# BOOSTXL-K350QVG-S1.net
KiCad netlist of a schematic drawn in Altium Designer
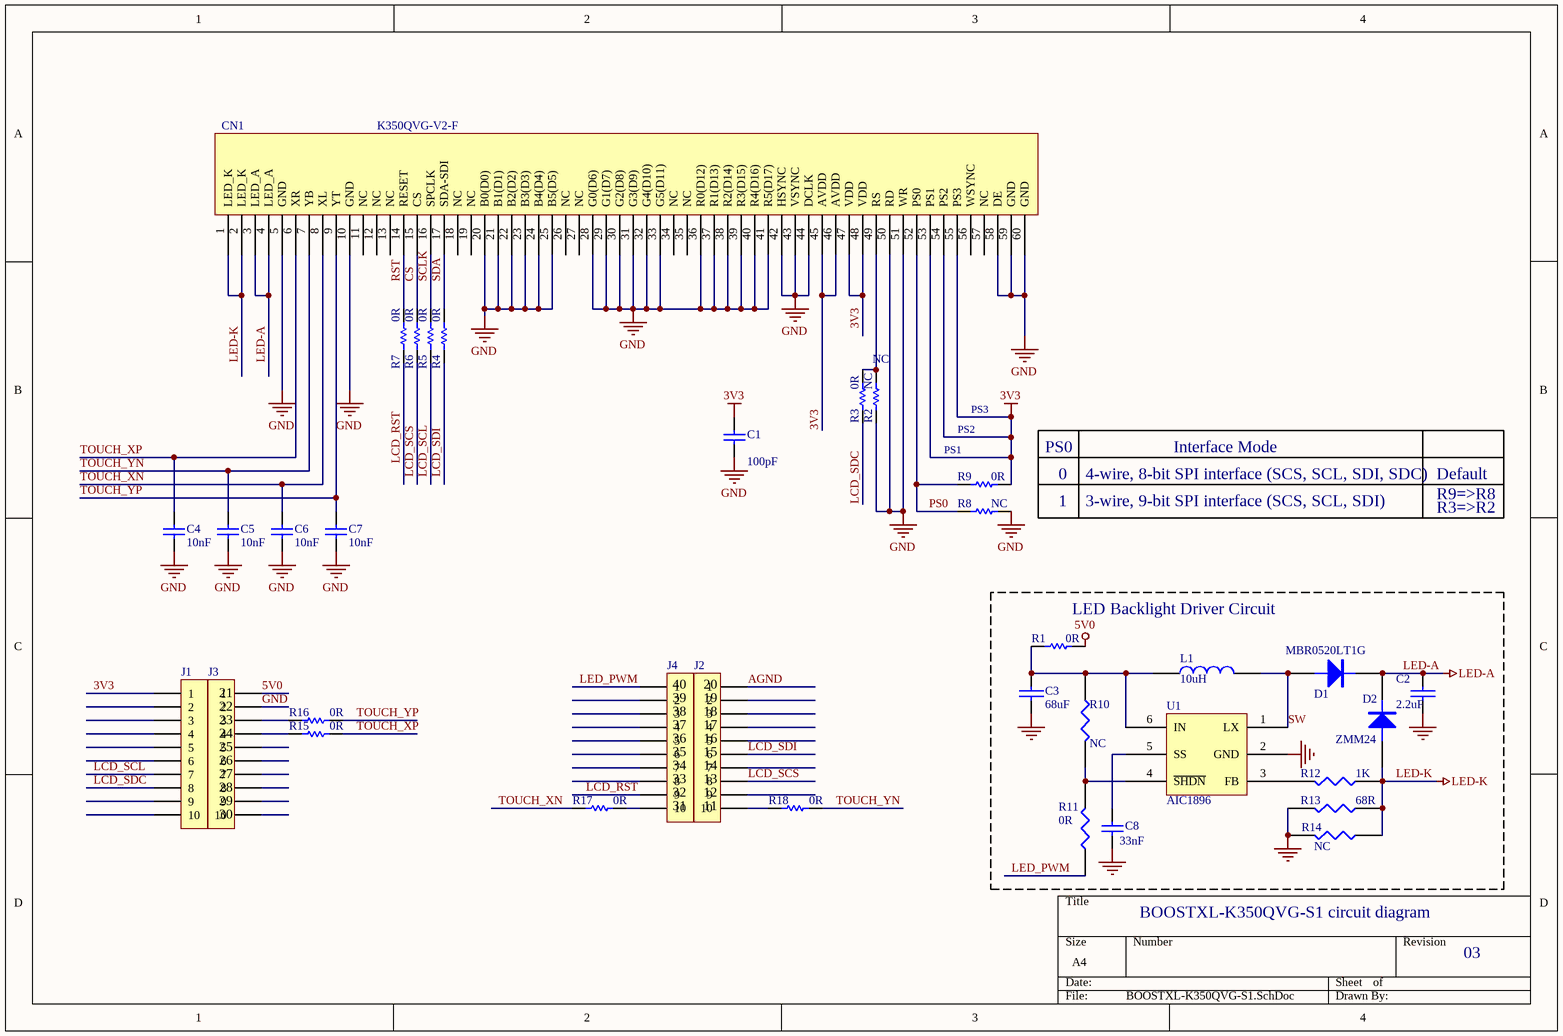
[diagram p0: BOOSTXL-K350QVG-S1.SchDoc]

(export (version "E")
  (design (tool "Eeschema 10.0.6"))
  (components
    (comp (ref "C1")
      (value "100pF")
      (footprint "1608[0603]")
      (description "Capacitor (Semiconductor SIM Model)")
      (fields (field (name "Comment") "0.1uF") (field (name "PUBLISHER") "Altium Limited"))
      (libsource (lib "Miscellaneous Devices") (part "Cap Semi"))
    )
    (comp (ref "C2")
      (value "2.2uF")
      (footprint "3225[1210]")
      (description "Capacitor")
      (libsource (lib "*") (part "CAP"))
    )
    (comp (ref "C3")
      (value "68uF")
      (footprint "TAN-C")
      (description "Capacitor")
      (libsource (lib "*") (part "CAP"))
    )
    (comp (ref "C4")
      (value "10nF")
      (footprint "1608[0603]")
      (description "Capacitor (Semiconductor SIM Model)")
      (fields (field (name "PUBLISHER") "Altium Limited"))
      (libsource (lib "Miscellaneous Devices") (part "Cap Semi"))
    )
    (comp (ref "C5")
      (value "10nF")
      (footprint "1608[0603]")
      (description "Capacitor (Semiconductor SIM Model)")
      (fields (field (name "PUBLISHER") "Altium Limited"))
      (libsource (lib "Miscellaneous Devices") (part "Cap Semi"))
    )
    (comp (ref "C6")
      (value "10nF")
      (footprint "1608[0603]")
      (description "Capacitor (Semiconductor SIM Model)")
      (fields (field (name "PUBLISHER") "Altium Limited"))
      (libsource (lib "Miscellaneous Devices") (part "Cap Semi"))
    )
    (comp (ref "C7")
      (value "10nF")
      (footprint "1608[0603]")
      (description "Capacitor (Semiconductor SIM Model)")
      (fields (field (name "PUBLISHER") "Altium Limited"))
      (libsource (lib "Miscellaneous Devices") (part "Cap Semi"))
    )
    (comp (ref "C8")
      (value "33nF")
      (footprint "1608[0603]")
      (description "Capacitor (Semiconductor SIM Model)")
      (fields (field (name "PUBLISHER") "Altium Limited"))
      (libsource (lib "Miscellaneous Devices") (part "Cap Semi"))
    )
    (comp (ref "CN1")
      (value "K350QVG-V2-F")
      (footprint "CON-K350-60")
      (libsource (lib "KEDlib") (part "K350QVG"))
    )
    (comp (ref "D1")
      (value "MBR0520LT1G")
      (footprint "DIODE")
      (description "Diode")
      (libsource (lib "*") (part "DIODE"))
    )
    (comp (ref "D2")
      (value "ZMM24")
      (footprint "DIODE")
      (description "Diode")
      (libsource (lib "*") (part "DIODE"))
    )
    (comp (ref "J1")
      (value "Socket 10")
      (footprint "HDR1X10")
      (description "Header, 10-Pin")
      (fields (field (name "PUBLISHER") "Altium Limited"))
      (libsource (lib "EB-StellarisLaunchPad-LCD") (part "Header 10"))
    )
    (comp (ref "J2")
      (value "Socket 10")
      (footprint "HDR1X10")
      (description "Header, 10-Pin")
      (fields (field (name "PUBLISHER") "Altium Limited"))
      (libsource (lib "") (part "Header 10_1"))
    )
    (comp (ref "J3")
      (value "Socket 10")
      (footprint "HDR1X10")
      (description "Header, 10-Pin")
      (fields (field (name "PUBLISHER") "Altium Limited"))
      (libsource (lib "") (part "Header 10_1"))
    )
    (comp (ref "J4")
      (value "Socket 10")
      (footprint "HDR1X10")
      (description "Header, 10-Pin")
      (fields (field (name "PUBLISHER") "Altium Limited"))
      (libsource (lib "EB-StellarisLaunchPad-LCD") (part "Header 10"))
    )
    (comp (ref "L1") (value "10uH") (footprint "IND") (libsource (lib "*") (part "INDUCTOR")))
    (comp (ref "R1")
      (value "0R")
      (footprint "1608[0603]")
      (description "Semiconductor Resistor")
      (fields (field (name "PUBLISHER") "Altium Limited"))
      (libsource (lib "Miscellaneous Devices") (part "Res Semi"))
    )
    (comp (ref "R2")
      (value "NC")
      (footprint "1608[0603]")
      (description "Semiconductor Resistor")
      (fields (field (name "ALTIUM_VALUE") "NC") (field (name "PUBLISHER") "Altium Limited"))
      (libsource (lib "Miscellaneous Devices") (part "Res Semi"))
    )
    (comp (ref "R3")
      (value "0R")
      (footprint "1608[0603]")
      (description "Semiconductor Resistor")
      (fields (field (name "PUBLISHER") "Altium Limited"))
      (libsource (lib "Miscellaneous Devices") (part "Res Semi"))
    )
    (comp (ref "R4")
      (value "0R")
      (footprint "1608[0603]")
      (description "Semiconductor Resistor")
      (fields (field (name "PUBLISHER") "Altium Limited"))
      (libsource (lib "Miscellaneous Devices") (part "Res Semi"))
    )
    (comp (ref "R5")
      (value "0R")
      (footprint "1608[0603]")
      (description "Semiconductor Resistor")
      (fields (field (name "PUBLISHER") "Altium Limited"))
      (libsource (lib "Miscellaneous Devices") (part "Res Semi"))
    )
    (comp (ref "R6")
      (value "0R")
      (footprint "1608[0603]")
      (description "Semiconductor Resistor")
      (fields (field (name "PUBLISHER") "Altium Limited"))
      (libsource (lib "Miscellaneous Devices") (part "Res Semi"))
    )
    (comp (ref "R7")
      (value "0R")
      (footprint "1608[0603]")
      (description "Semiconductor Resistor")
      (fields (field (name "PUBLISHER") "Altium Limited"))
      (libsource (lib "Miscellaneous Devices") (part "Res Semi"))
    )
    (comp (ref "R8")
      (value "NC")
      (footprint "1608[0603]")
      (description "Semiconductor Resistor")
      (fields (field (name "PUBLISHER") "Altium Limited"))
      (libsource (lib "Miscellaneous Devices") (part "Res Semi"))
    )
    (comp (ref "R9")
      (value "0R")
      (footprint "1608[0603]")
      (description "Semiconductor Resistor")
      (fields (field (name "PUBLISHER") "Altium Limited"))
      (libsource (lib "Miscellaneous Devices") (part "Res Semi"))
    )
    (comp (ref "R10") (value "NC") (footprint "1608[0603]") (libsource (lib "*") (part "RES1")))
    (comp (ref "R11") (value "0R") (footprint "1608[0603]") (libsource (lib "*") (part "RES1")))
    (comp (ref "R12") (value "1K") (footprint "1608[0603]") (libsource (lib "*") (part "RES1")))
    (comp (ref "R13") (value "68R") (footprint "1608[0603]") (libsource (lib "*") (part "RES1")))
    (comp (ref "R14") (value "NC") (footprint "1608[0603]") (libsource (lib "*") (part "RES1")))
    (comp (ref "R15")
      (value "0R")
      (footprint "1608[0603]")
      (description "Semiconductor Resistor")
      (fields (field (name "PUBLISHER") "Altium Limited"))
      (libsource (lib "Miscellaneous Devices") (part "Res Semi"))
    )
    (comp (ref "R16")
      (value "0R")
      (footprint "1608[0603]")
      (description "Semiconductor Resistor")
      (fields (field (name "PUBLISHER") "Altium Limited"))
      (libsource (lib "Miscellaneous Devices") (part "Res Semi"))
    )
    (comp (ref "R17")
      (value "0R")
      (footprint "1608[0603]")
      (description "Semiconductor Resistor")
      (fields (field (name "PUBLISHER") "Altium Limited"))
      (libsource (lib "Miscellaneous Devices") (part "Res Semi"))
    )
    (comp (ref "R18")
      (value "0R")
      (footprint "1608[0603]")
      (description "Semiconductor Resistor")
      (fields (field (name "PUBLISHER") "Altium Limited"))
      (libsource (lib "Miscellaneous Devices") (part "Res Semi"))
    )
    (comp (ref "U1")
      (value "AIC1896")
      (footprint "SOT-23-6")
      (libsource (lib "EB-StellarisLaunchPad-LCD") (part "AIC1896"))
    )
  )
  (nets
    (net (code "1") (name "/CS") (class "Default")
      (node (ref "CN1") (pin "15") (pinfunction "CS_15") (pintype "passive"))
      (node (ref "R6") (pin "2") (pinfunction "2_2") (pintype "passive"))
    )
    (net (code "2") (name "/LCD_RST") (class "Default")
      (node (ref "J4") (pin "9") (pinfunction "9_9") (pintype "passive"))
      (node (ref "R7") (pin "1") (pinfunction "1_1") (pintype "passive"))
    )
    (net (code "3") (name "/LCD_SCL") (class "Default")
      (node (ref "J1") (pin "7") (pinfunction "7_7") (pintype "passive"))
      (node (ref "R5") (pin "1") (pinfunction "1_1") (pintype "passive"))
    )
    (net (code "4") (name "/LCD_SCS") (class "Default")
      (node (ref "J2") (pin "8") (pinfunction "8_8") (pintype "passive"))
      (node (ref "R6") (pin "1") (pinfunction "1_1") (pintype "passive"))
    )
    (net (code "5") (name "/LCD_SDC") (class "Default")
      (node (ref "J1") (pin "8") (pinfunction "8_8") (pintype "passive"))
      (node (ref "R3") (pin "1") (pinfunction "1_1") (pintype "passive"))
    )
    (net (code "6") (name "/LCD_SDI") (class "Default")
      (node (ref "J2") (pin "6") (pinfunction "6_6") (pintype "passive"))
      (node (ref "R4") (pin "1") (pinfunction "1_1") (pintype "passive"))
    )
    (net (code "7") (name "/LED_PWM") (class "Default")
      (node (ref "J4") (pin "1") (pinfunction "1_1") (pintype "passive"))
      (node (ref "R11") (pin "1") (pinfunction "1_1") (pintype "passive"))
    )
    (net (code "8") (name "/PS0") (class "Default")
      (node (ref "CN1") (pin "52") (pinfunction "PS0_52") (pintype "passive"))
      (node (ref "R8") (pin "1") (pinfunction "1_1") (pintype "passive"))
      (node (ref "R9") (pin "1") (pinfunction "1_1") (pintype "passive"))
    )
    (net (code "9") (name "/RST") (class "Default")
      (node (ref "CN1") (pin "14") (pinfunction "RESET_14") (pintype "passive"))
      (node (ref "R7") (pin "2") (pinfunction "2_2") (pintype "passive"))
    )
    (net (code "10") (name "/SCLK") (class "Default")
      (node (ref "CN1") (pin "16") (pinfunction "SPCLK_16") (pintype "passive"))
      (node (ref "R5") (pin "2") (pinfunction "2_2") (pintype "passive"))
    )
    (net (code "11") (name "/SDA") (class "Default")
      (node (ref "CN1") (pin "17") (pinfunction "SDA-SDI_17") (pintype "passive"))
      (node (ref "R4") (pin "2") (pinfunction "2_2") (pintype "passive"))
    )
    (net (code "12") (name "/SW") (class "Default")
      (node (ref "D1") (pin "A") (pinfunction "A_A") (pintype "passive"))
      (node (ref "L1") (pin "2") (pinfunction "2_2") (pintype "passive"))
      (node (ref "U1") (pin "1") (pinfunction "LX_1") (pintype "passive"))
    )
    (net (code "13") (name "/TOUCH_XN") (class "Default")
      (node (ref "C6") (pin "2") (pinfunction "2_2") (pintype "passive"))
      (node (ref "CN1") (pin "8") (pinfunction "XL_8") (pintype "passive"))
      (node (ref "R17") (pin "1") (pinfunction "1_1") (pintype "passive"))
    )
    (net (code "14") (name "/TOUCH_XP") (class "Default")
      (node (ref "C4") (pin "2") (pinfunction "2_2") (pintype "passive"))
      (node (ref "CN1") (pin "6") (pinfunction "XR_6") (pintype "passive"))
      (node (ref "R15") (pin "2") (pinfunction "2_2") (pintype "passive"))
    )
    (net (code "15") (name "/TOUCH_YN") (class "Default")
      (node (ref "C5") (pin "2") (pinfunction "2_2") (pintype "passive"))
      (node (ref "CN1") (pin "7") (pinfunction "YB_7") (pintype "passive"))
      (node (ref "R18") (pin "2") (pinfunction "2_2") (pintype "passive"))
    )
    (net (code "16") (name "/TOUCH_YP") (class "Default")
      (node (ref "C7") (pin "2") (pinfunction "2_2") (pintype "passive"))
      (node (ref "CN1") (pin "9") (pinfunction "YT_9") (pintype "passive"))
      (node (ref "R16") (pin "2") (pinfunction "2_2") (pintype "passive"))
    )
    (net (code "17") (name "3V3") (class "Default")
      (node (ref "C1") (pin "2") (pinfunction "2_2") (pintype "passive"))
      (node (ref "CN1") (pin "45") (pinfunction "AVDD_45") (pintype "passive"))
      (node (ref "CN1") (pin "46") (pinfunction "AVDD_46") (pintype "passive"))
      (node (ref "CN1") (pin "47") (pinfunction "VDD_47") (pintype "passive"))
      (node (ref "CN1") (pin "48") (pinfunction "VDD_48") (pintype "passive"))
      (node (ref "CN1") (pin "53") (pinfunction "PS1_53") (pintype "passive"))
      (node (ref "CN1") (pin "54") (pinfunction "PS2_54") (pintype "passive"))
      (node (ref "CN1") (pin "55") (pinfunction "PS3_55") (pintype "passive"))
      (node (ref "J1") (pin "1") (pinfunction "1_1") (pintype "passive"))
      (node (ref "R9") (pin "2") (pinfunction "2_2") (pintype "passive"))
    )
    (net (code "18") (name "5V0") (class "Default")
      (node (ref "J3") (pin "1") (pinfunction "1_1") (pintype "passive"))
      (node (ref "R1") (pin "2") (pinfunction "2_2") (pintype "passive"))
    )
    (net (code "19") (name "AGND") (class "Default")
      (node (ref "C2") (pin "1") (pinfunction "1_1") (pintype "passive"))
      (node (ref "C3") (pin "2") (pinfunction "2_2") (pintype "passive"))
      (node (ref "C8") (pin "1") (pinfunction "1_1") (pintype "passive"))
      (node (ref "J2") (pin "1") (pinfunction "1_1") (pintype "passive"))
      (node (ref "R13") (pin "2") (pinfunction "2_2") (pintype "passive"))
      (node (ref "R14") (pin "2") (pinfunction "2_2") (pintype "passive"))
    )
    (net (code "20") (name "GND") (class "Default")
      (node (ref "C1") (pin "1") (pinfunction "1_1") (pintype "passive"))
      (node (ref "C4") (pin "1") (pinfunction "1_1") (pintype "passive"))
      (node (ref "C5") (pin "1") (pinfunction "1_1") (pintype "passive"))
      (node (ref "C6") (pin "1") (pinfunction "1_1") (pintype "passive"))
      (node (ref "C7") (pin "1") (pinfunction "1_1") (pintype "passive"))
      (node (ref "CN1") (pin "10") (pinfunction "GND_10") (pintype "passive"))
      (node (ref "CN1") (pin "20") (pinfunction "B0(D0)_20") (pintype "passive"))
      (node (ref "CN1") (pin "21") (pinfunction "B1(D1)_21") (pintype "passive"))
      (node (ref "CN1") (pin "22") (pinfunction "B2(D2)_22") (pintype "passive"))
      (node (ref "CN1") (pin "23") (pinfunction "B3(D3)_23") (pintype "passive"))
      (node (ref "CN1") (pin "24") (pinfunction "B4(D4)_24") (pintype "passive"))
      (node (ref "CN1") (pin "25") (pinfunction "B5(D5)_25") (pintype "passive"))
      (node (ref "CN1") (pin "28") (pinfunction "G0(D6)_28") (pintype "passive"))
      (node (ref "CN1") (pin "29") (pinfunction "G1(D7)_29") (pintype "passive"))
      (node (ref "CN1") (pin "30") (pinfunction "G2(D8)_30") (pintype "passive"))
      (node (ref "CN1") (pin "31") (pinfunction "G3(D9)_31") (pintype "passive"))
      (node (ref "CN1") (pin "32") (pinfunction "G4(D10)_32") (pintype "passive"))
      (node (ref "CN1") (pin "33") (pinfunction "G5(D11)_33") (pintype "passive"))
      (node (ref "CN1") (pin "36") (pinfunction "R0(D12)_36") (pintype "passive"))
      (node (ref "CN1") (pin "37") (pinfunction "R1(D13)_37") (pintype "passive"))
      (node (ref "CN1") (pin "38") (pinfunction "R2(D14)_38") (pintype "passive"))
      (node (ref "CN1") (pin "39") (pinfunction "R3(D15)_39") (pintype "passive"))
      (node (ref "CN1") (pin "40") (pinfunction "R4(D16)_40") (pintype "passive"))
      (node (ref "CN1") (pin "41") (pinfunction "R5(D17)_41") (pintype "passive"))
      (node (ref "CN1") (pin "42") (pinfunction "HSYNC_42") (pintype "passive"))
      (node (ref "CN1") (pin "43") (pinfunction "VSYNC_43") (pintype "passive"))
      (node (ref "CN1") (pin "44") (pinfunction "DCLK_44") (pintype "passive"))
      (node (ref "CN1") (pin "5") (pinfunction "GND_5") (pintype "passive"))
      (node (ref "CN1") (pin "50") (pinfunction "RD_50") (pintype "passive"))
      (node (ref "CN1") (pin "51") (pinfunction "WR_51") (pintype "passive"))
      (node (ref "CN1") (pin "58") (pinfunction "DE_58") (pintype "passive"))
      (node (ref "CN1") (pin "59") (pinfunction "GND_59") (pintype "passive"))
      (node (ref "CN1") (pin "60") (pinfunction "GND_60") (pintype "passive"))
      (node (ref "J3") (pin "2") (pinfunction "2_2") (pintype "passive"))
      (node (ref "R2") (pin "1") (pinfunction "1_1") (pintype "passive"))
      (node (ref "R8") (pin "2") (pinfunction "2_2") (pintype "passive"))
      (node (ref "U1") (pin "2") (pinfunction "GND_2") (pintype "passive"))
    )
    (net (code "21") (name "LED-A") (class "Default")
      (node (ref "C2") (pin "2") (pinfunction "2_2") (pintype "passive"))
      (node (ref "CN1") (pin "3") (pinfunction "LED_A_3") (pintype "passive"))
      (node (ref "CN1") (pin "4") (pinfunction "LED_A_4") (pintype "passive"))
      (node (ref "D1") (pin "K") (pinfunction "K_K") (pintype "passive"))
      (node (ref "D2") (pin "K") (pinfunction "K_K") (pintype "passive"))
    )
    (net (code "22") (name "LED-K") (class "Default")
      (node (ref "CN1") (pin "1") (pinfunction "LED_K_1") (pintype "passive"))
      (node (ref "CN1") (pin "2") (pinfunction "LED_K_2") (pintype "passive"))
      (node (ref "D2") (pin "A") (pinfunction "A_A") (pintype "passive"))
      (node (ref "R12") (pin "1") (pinfunction "1_1") (pintype "passive"))
      (node (ref "R13") (pin "1") (pinfunction "1_1") (pintype "passive"))
      (node (ref "R14") (pin "1") (pinfunction "1_1") (pintype "passive"))
    )
    (net (code "23") (name "Net-(CN1-RS)") (class "Default")
      (node (ref "CN1") (pin "49") (pinfunction "RS_49") (pintype "passive"))
      (node (ref "R2") (pin "2") (pinfunction "2_2") (pintype "passive"))
      (node (ref "R3") (pin "2") (pinfunction "2_2") (pintype "passive"))
    )
    (net (code "24") (name "Net-(J2-Pad10)") (class "Default")
      (node (ref "J2") (pin "10") (pinfunction "10_10") (pintype "passive"))
      (node (ref "R18") (pin "1") (pinfunction "1_1") (pintype "passive"))
    )
    (net (code "25") (name "Net-(J3-Pad3)") (class "Default")
      (node (ref "J3") (pin "3") (pinfunction "3_3") (pintype "passive"))
      (node (ref "R16") (pin "1") (pinfunction "1_1") (pintype "passive"))
    )
    (net (code "26") (name "Net-(J3-Pad4)") (class "Default")
      (node (ref "J3") (pin "4") (pinfunction "4_4") (pintype "passive"))
      (node (ref "R15") (pin "1") (pinfunction "1_1") (pintype "passive"))
    )
    (net (code "27") (name "Net-(J4-Pad10)") (class "Default")
      (node (ref "J4") (pin "10") (pinfunction "10_10") (pintype "passive"))
      (node (ref "R17") (pin "2") (pinfunction "2_2") (pintype "passive"))
    )
    (net (code "28") (name "Net-(U1-FB)") (class "Default")
      (node (ref "R12") (pin "2") (pinfunction "2_2") (pintype "passive"))
      (node (ref "U1") (pin "3") (pinfunction "FB_3") (pintype "passive"))
    )
    (net (code "29") (name "Net-(U1-IN)") (class "Default")
      (node (ref "C3") (pin "1") (pinfunction "1_1") (pintype "passive"))
      (node (ref "L1") (pin "1") (pinfunction "1_1") (pintype "passive"))
      (node (ref "R1") (pin "1") (pinfunction "1_1") (pintype "passive"))
      (node (ref "R10") (pin "1") (pinfunction "1_1") (pintype "passive"))
      (node (ref "U1") (pin "6") (pinfunction "IN_6") (pintype "passive"))
    )
    (net (code "30") (name "Net-(U1-SS)") (class "Default")
      (node (ref "C8") (pin "2") (pinfunction "2_2") (pintype "passive"))
      (node (ref "U1") (pin "5") (pinfunction "SS_5") (pintype "passive"))
    )
    (net (code "31") (name "Net-(U1-~{SHDN})") (class "Default")
      (node (ref "R10") (pin "2") (pinfunction "2_2") (pintype "passive"))
      (node (ref "R11") (pin "2") (pinfunction "2_2") (pintype "passive"))
      (node (ref "U1") (pin "4") (pinfunction "~{SHDN}_4") (pintype "passive"))
    )
    (net (code "32") (name "unconnected-(CN1-NC-Pad11)") (class "Default")
      (node (ref "CN1") (pin "11") (pinfunction "NC_11") (pintype "passive"))
    )
    (net (code "33") (name "unconnected-(CN1-NC-Pad12)") (class "Default")
      (node (ref "CN1") (pin "12") (pinfunction "NC_12") (pintype "passive"))
    )
    (net (code "34") (name "unconnected-(CN1-NC-Pad13)") (class "Default")
      (node (ref "CN1") (pin "13") (pinfunction "NC_13") (pintype "passive"))
    )
    (net (code "35") (name "unconnected-(CN1-NC-Pad18)") (class "Default")
      (node (ref "CN1") (pin "18") (pinfunction "NC_18") (pintype "passive"))
    )
    (net (code "36") (name "unconnected-(CN1-NC-Pad19)") (class "Default")
      (node (ref "CN1") (pin "19") (pinfunction "NC_19") (pintype "passive"))
    )
    (net (code "37") (name "unconnected-(CN1-NC-Pad26)") (class "Default")
      (node (ref "CN1") (pin "26") (pinfunction "NC_26") (pintype "passive"))
    )
    (net (code "38") (name "unconnected-(CN1-NC-Pad27)") (class "Default")
      (node (ref "CN1") (pin "27") (pinfunction "NC_27") (pintype "passive"))
    )
    (net (code "39") (name "unconnected-(CN1-NC-Pad34)") (class "Default")
      (node (ref "CN1") (pin "34") (pinfunction "NC_34") (pintype "passive"))
    )
    (net (code "40") (name "unconnected-(CN1-NC-Pad35)") (class "Default")
      (node (ref "CN1") (pin "35") (pinfunction "NC_35") (pintype "passive"))
    )
    (net (code "41") (name "unconnected-(CN1-NC-Pad57)") (class "Default")
      (node (ref "CN1") (pin "57") (pinfunction "NC_57") (pintype "passive"))
    )
    (net (code "42") (name "unconnected-(CN1-WSYNC-Pad56)") (class "Default")
      (node (ref "CN1") (pin "56") (pinfunction "WSYNC_56") (pintype "passive"))
    )
    (net (code "43") (name "unconnected-(J1-Pad2)") (class "Default")
      (node (ref "J1") (pin "2") (pinfunction "2_2") (pintype "passive"))
    )
    (net (code "44") (name "unconnected-(J1-Pad3)") (class "Default")
      (node (ref "J1") (pin "3") (pinfunction "3_3") (pintype "passive"))
    )
    (net (code "45") (name "unconnected-(J1-Pad4)") (class "Default")
      (node (ref "J1") (pin "4") (pinfunction "4_4") (pintype "passive"))
    )
    (net (code "46") (name "unconnected-(J1-Pad5)") (class "Default")
      (node (ref "J1") (pin "5") (pinfunction "5_5") (pintype "passive"))
    )
    (net (code "47") (name "unconnected-(J1-Pad6)") (class "Default")
      (node (ref "J1") (pin "6") (pinfunction "6_6") (pintype "passive"))
    )
    (net (code "48") (name "unconnected-(J1-Pad9)") (class "Default")
      (node (ref "J1") (pin "9") (pinfunction "9_9") (pintype "passive"))
    )
    (net (code "49") (name "unconnected-(J1-Pad10)") (class "Default")
      (node (ref "J1") (pin "10") (pinfunction "10_10") (pintype "passive"))
    )
    (net (code "50") (name "unconnected-(J2-Pad2)") (class "Default")
      (node (ref "J2") (pin "2") (pinfunction "2_2") (pintype "passive"))
    )
    (net (code "51") (name "unconnected-(J2-Pad3)") (class "Default")
      (node (ref "J2") (pin "3") (pinfunction "3_3") (pintype "passive"))
    )
    (net (code "52") (name "unconnected-(J2-Pad4)") (class "Default")
      (node (ref "J2") (pin "4") (pinfunction "4_4") (pintype "passive"))
    )
    (net (code "53") (name "unconnected-(J2-Pad5)") (class "Default")
      (node (ref "J2") (pin "5") (pinfunction "5_5") (pintype "passive"))
    )
    (net (code "54") (name "unconnected-(J2-Pad7)") (class "Default")
      (node (ref "J2") (pin "7") (pinfunction "7_7") (pintype "passive"))
    )
    (net (code "55") (name "unconnected-(J2-Pad9)") (class "Default")
      (node (ref "J2") (pin "9") (pinfunction "9_9") (pintype "passive"))
    )
    (net (code "56") (name "unconnected-(J3-Pad5)") (class "Default")
      (node (ref "J3") (pin "5") (pinfunction "5_5") (pintype "passive"))
    )
    (net (code "57") (name "unconnected-(J3-Pad6)") (class "Default")
      (node (ref "J3") (pin "6") (pinfunction "6_6") (pintype "passive"))
    )
    (net (code "58") (name "unconnected-(J3-Pad7)") (class "Default")
      (node (ref "J3") (pin "7") (pinfunction "7_7") (pintype "passive"))
    )
    (net (code "59") (name "unconnected-(J3-Pad8)") (class "Default")
      (node (ref "J3") (pin "8") (pinfunction "8_8") (pintype "passive"))
    )
    (net (code "60") (name "unconnected-(J3-Pad9)") (class "Default")
      (node (ref "J3") (pin "9") (pinfunction "9_9") (pintype "passive"))
    )
    (net (code "61") (name "unconnected-(J3-Pad10)") (class "Default")
      (node (ref "J3") (pin "10") (pinfunction "10_10") (pintype "passive"))
    )
    (net (code "62") (name "unconnected-(J4-Pad2)") (class "Default")
      (node (ref "J4") (pin "2") (pinfunction "2_2") (pintype "passive"))
    )
    (net (code "63") (name "unconnected-(J4-Pad3)") (class "Default")
      (node (ref "J4") (pin "3") (pinfunction "3_3") (pintype "passive"))
    )
    (net (code "64") (name "unconnected-(J4-Pad4)") (class "Default")
      (node (ref "J4") (pin "4") (pinfunction "4_4") (pintype "passive"))
    )
    (net (code "65") (name "unconnected-(J4-Pad5)") (class "Default")
      (node (ref "J4") (pin "5") (pinfunction "5_5") (pintype "passive"))
    )
    (net (code "66") (name "unconnected-(J4-Pad6)") (class "Default")
      (node (ref "J4") (pin "6") (pinfunction "6_6") (pintype "passive"))
    )
    (net (code "67") (name "unconnected-(J4-Pad7)") (class "Default")
      (node (ref "J4") (pin "7") (pinfunction "7_7") (pintype "passive"))
    )
    (net (code "68") (name "unconnected-(J4-Pad8)") (class "Default")
      (node (ref "J4") (pin "8") (pinfunction "8_8") (pintype "passive"))
    )
  )
)
